# fpga.net
KiCad netlist of a schematic drawn in Altium Designer
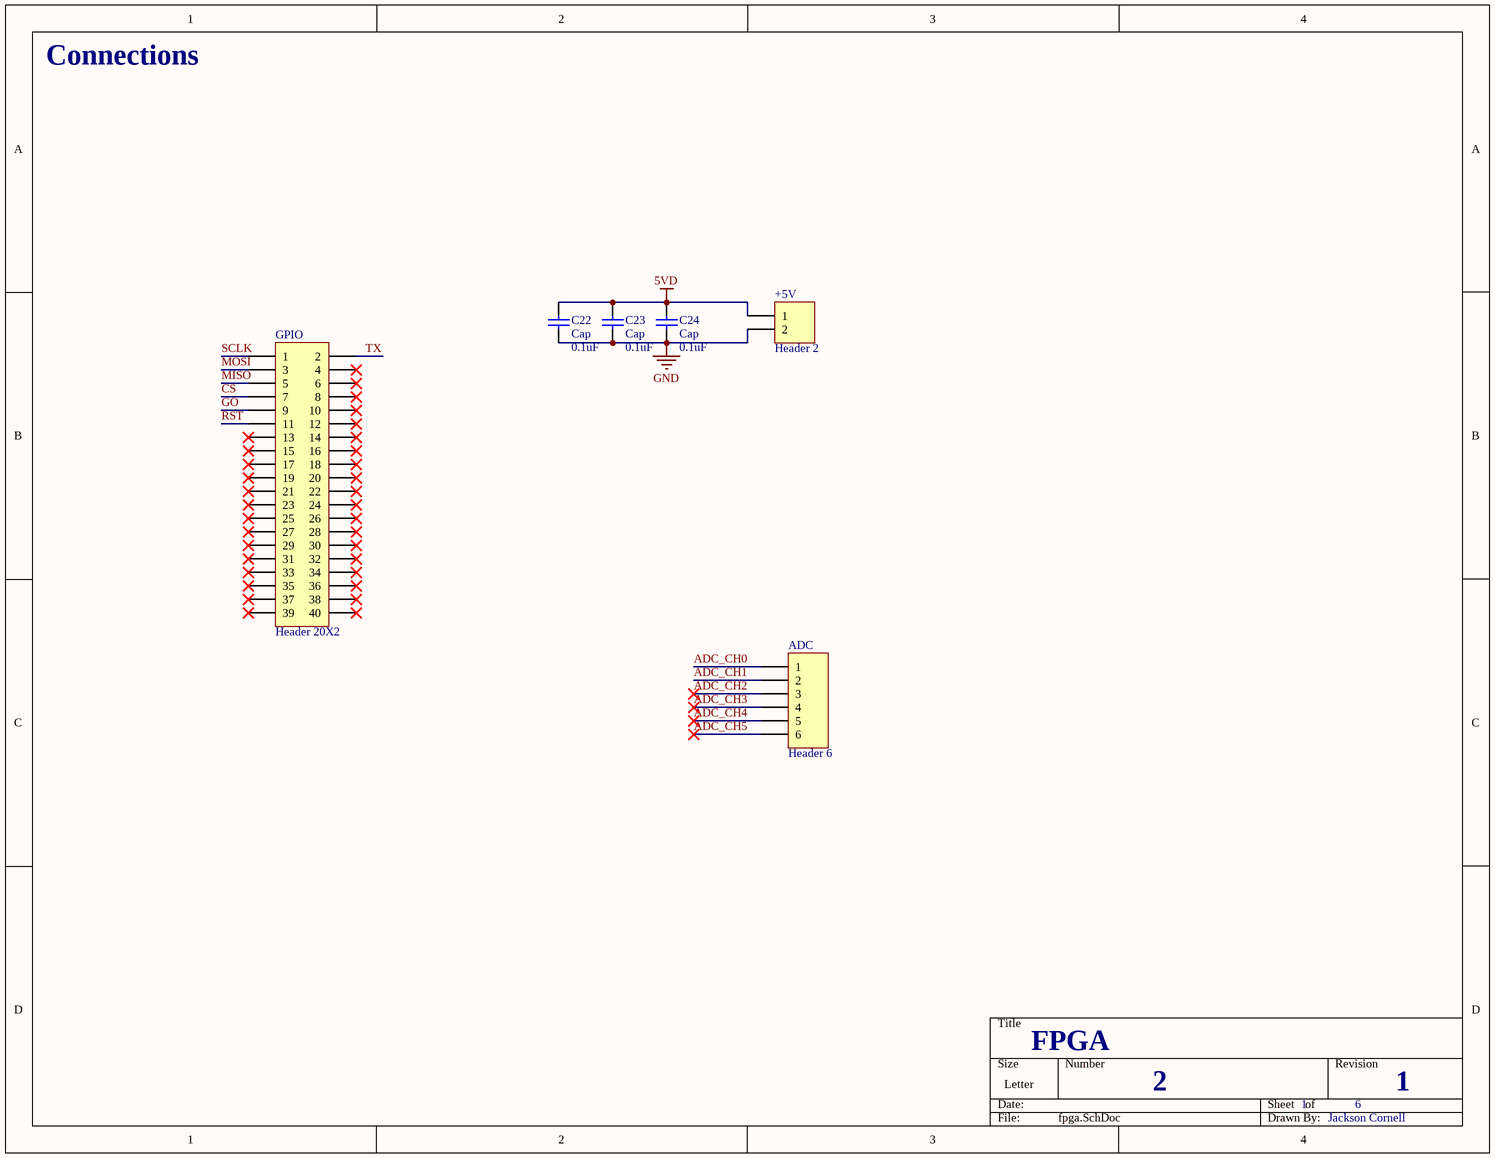
[diagram p0: fpga.SchDoc]

(export (version "E")
  (design (tool "Eeschema 10.0.6"))
  (components
    (comp (ref "+5V")
      (value "Header 2")
      (footprint "HDR1X2")
      (description "Header, 2-Pin")
      (fields (field (name "PUBLISHER") "Altium Limited"))
      (libsource (lib "Miscellaneous Connectors") (part "Header 2"))
    )
    (comp (ref "ADC")
      (value "Header 6")
      (footprint "HDR1X6")
      (description "Header, 6-Pin")
      (fields (field (name "PUBLISHER") "Altium Limited"))
      (libsource (lib "Miscellaneous Connectors") (part "Header 6"))
    )
    (comp (ref "C22")
      (value "Cap")
      (footprint "CAPC0805")
      (description "Capacitor")
      (fields (field (name "ALTIUM_VALUE") "0.1uF") (field (name "PUBLISHER") "Altium Limited"))
      (libsource (lib "Miscellaneous Devices") (part "Cap"))
    )
    (comp (ref "C23")
      (value "Cap")
      (footprint "CAPC0805")
      (description "Capacitor")
      (fields (field (name "ALTIUM_VALUE") "0.1uF") (field (name "PUBLISHER") "Altium Limited"))
      (libsource (lib "Miscellaneous Devices") (part "Cap"))
    )
    (comp (ref "C24")
      (value "Cap")
      (footprint "CAPC0805")
      (description "Capacitor")
      (fields (field (name "ALTIUM_VALUE") "0.1uF") (field (name "PUBLISHER") "Altium Limited"))
      (libsource (lib "Miscellaneous Devices") (part "Cap"))
    )
    (comp (ref "GPIO")
      (value "Header 20X2")
      (footprint "HDR2X20")
      (description "Header, 20-Pin, Dual row")
      (fields (field (name "PUBLISHER") "Altium Limited"))
      (libsource (lib "Miscellaneous Connectors") (part "Header 20X2"))
    )
  )
  (nets
    (net (code "1") (name "/ADC_CH0") (class "Default")
      (node (ref "ADC") (pin "1") (pinfunction "1_1") (pintype "passive"))
    )
    (net (code "2") (name "/ADC_CH1") (class "Default")
      (node (ref "ADC") (pin "2") (pinfunction "2_2") (pintype "passive"))
    )
    (net (code "3") (name "/ADC_CH2") (class "Default")
      (node (ref "ADC") (pin "3") (pinfunction "3_3") (pintype "passive+no_connect"))
    )
    (net (code "4") (name "/ADC_CH3") (class "Default")
      (node (ref "ADC") (pin "4") (pinfunction "4_4") (pintype "passive+no_connect"))
    )
    (net (code "5") (name "/ADC_CH4") (class "Default")
      (node (ref "ADC") (pin "5") (pinfunction "5_5") (pintype "passive+no_connect"))
    )
    (net (code "6") (name "/ADC_CH5") (class "Default")
      (node (ref "ADC") (pin "6") (pinfunction "6_6") (pintype "passive+no_connect"))
    )
    (net (code "7") (name "/CS") (class "Default")
      (node (ref "GPIO") (pin "7") (pinfunction "7_7") (pintype "passive"))
    )
    (net (code "8") (name "/GO") (class "Default")
      (node (ref "GPIO") (pin "9") (pinfunction "9_9") (pintype "passive"))
    )
    (net (code "9") (name "/MISO") (class "Default")
      (node (ref "GPIO") (pin "5") (pinfunction "5_5") (pintype "passive"))
    )
    (net (code "10") (name "/MOSI") (class "Default")
      (node (ref "GPIO") (pin "3") (pinfunction "3_3") (pintype "passive"))
    )
    (net (code "11") (name "/RST") (class "Default")
      (node (ref "GPIO") (pin "11") (pinfunction "11_11") (pintype "passive"))
    )
    (net (code "12") (name "/SCLK") (class "Default")
      (node (ref "GPIO") (pin "1") (pinfunction "1_1") (pintype "passive"))
    )
    (net (code "13") (name "/TX") (class "Default")
      (node (ref "GPIO") (pin "2") (pinfunction "2_2") (pintype "passive"))
    )
    (net (code "14") (name "5VD") (class "Default")
      (node (ref "+5V") (pin "1") (pinfunction "1_1") (pintype "passive"))
      (node (ref "C22") (pin "2") (pinfunction "2_2") (pintype "passive"))
      (node (ref "C23") (pin "2") (pinfunction "2_2") (pintype "passive"))
      (node (ref "C24") (pin "2") (pinfunction "2_2") (pintype "passive"))
    )
    (net (code "15") (name "GND") (class "Default")
      (node (ref "+5V") (pin "2") (pinfunction "2_2") (pintype "passive"))
      (node (ref "C22") (pin "1") (pinfunction "1_1") (pintype "passive"))
      (node (ref "C23") (pin "1") (pinfunction "1_1") (pintype "passive"))
      (node (ref "C24") (pin "1") (pinfunction "1_1") (pintype "passive"))
    )
    (net (code "16") (name "unconnected-(GPIO-Pad4)") (class "Default")
      (node (ref "GPIO") (pin "4") (pinfunction "4_4") (pintype "passive+no_connect"))
    )
    (net (code "17") (name "unconnected-(GPIO-Pad6)") (class "Default")
      (node (ref "GPIO") (pin "6") (pinfunction "6_6") (pintype "passive+no_connect"))
    )
    (net (code "18") (name "unconnected-(GPIO-Pad8)") (class "Default")
      (node (ref "GPIO") (pin "8") (pinfunction "8_8") (pintype "passive+no_connect"))
    )
    (net (code "19") (name "unconnected-(GPIO-Pad10)") (class "Default")
      (node (ref "GPIO") (pin "10") (pinfunction "10_10") (pintype "passive+no_connect"))
    )
    (net (code "20") (name "unconnected-(GPIO-Pad12)") (class "Default")
      (node (ref "GPIO") (pin "12") (pinfunction "12_12") (pintype "passive+no_connect"))
    )
    (net (code "21") (name "unconnected-(GPIO-Pad13)") (class "Default")
      (node (ref "GPIO") (pin "13") (pinfunction "13_13") (pintype "passive+no_connect"))
    )
    (net (code "22") (name "unconnected-(GPIO-Pad14)") (class "Default")
      (node (ref "GPIO") (pin "14") (pinfunction "14_14") (pintype "passive+no_connect"))
    )
    (net (code "23") (name "unconnected-(GPIO-Pad15)") (class "Default")
      (node (ref "GPIO") (pin "15") (pinfunction "15_15") (pintype "passive+no_connect"))
    )
    (net (code "24") (name "unconnected-(GPIO-Pad16)") (class "Default")
      (node (ref "GPIO") (pin "16") (pinfunction "16_16") (pintype "passive+no_connect"))
    )
    (net (code "25") (name "unconnected-(GPIO-Pad17)") (class "Default")
      (node (ref "GPIO") (pin "17") (pinfunction "17_17") (pintype "passive+no_connect"))
    )
    (net (code "26") (name "unconnected-(GPIO-Pad18)") (class "Default")
      (node (ref "GPIO") (pin "18") (pinfunction "18_18") (pintype "passive+no_connect"))
    )
    (net (code "27") (name "unconnected-(GPIO-Pad19)") (class "Default")
      (node (ref "GPIO") (pin "19") (pinfunction "19_19") (pintype "passive+no_connect"))
    )
    (net (code "28") (name "unconnected-(GPIO-Pad20)") (class "Default")
      (node (ref "GPIO") (pin "20") (pinfunction "20_20") (pintype "passive+no_connect"))
    )
    (net (code "29") (name "unconnected-(GPIO-Pad21)") (class "Default")
      (node (ref "GPIO") (pin "21") (pinfunction "21_21") (pintype "passive+no_connect"))
    )
    (net (code "30") (name "unconnected-(GPIO-Pad22)") (class "Default")
      (node (ref "GPIO") (pin "22") (pinfunction "22_22") (pintype "passive+no_connect"))
    )
    (net (code "31") (name "unconnected-(GPIO-Pad23)") (class "Default")
      (node (ref "GPIO") (pin "23") (pinfunction "23_23") (pintype "passive+no_connect"))
    )
    (net (code "32") (name "unconnected-(GPIO-Pad24)") (class "Default")
      (node (ref "GPIO") (pin "24") (pinfunction "24_24") (pintype "passive+no_connect"))
    )
    (net (code "33") (name "unconnected-(GPIO-Pad25)") (class "Default")
      (node (ref "GPIO") (pin "25") (pinfunction "25_25") (pintype "passive+no_connect"))
    )
    (net (code "34") (name "unconnected-(GPIO-Pad26)") (class "Default")
      (node (ref "GPIO") (pin "26") (pinfunction "26_26") (pintype "passive+no_connect"))
    )
    (net (code "35") (name "unconnected-(GPIO-Pad27)") (class "Default")
      (node (ref "GPIO") (pin "27") (pinfunction "27_27") (pintype "passive+no_connect"))
    )
    (net (code "36") (name "unconnected-(GPIO-Pad28)") (class "Default")
      (node (ref "GPIO") (pin "28") (pinfunction "28_28") (pintype "passive+no_connect"))
    )
    (net (code "37") (name "unconnected-(GPIO-Pad29)") (class "Default")
      (node (ref "GPIO") (pin "29") (pinfunction "29_29") (pintype "passive+no_connect"))
    )
    (net (code "38") (name "unconnected-(GPIO-Pad30)") (class "Default")
      (node (ref "GPIO") (pin "30") (pinfunction "30_30") (pintype "passive+no_connect"))
    )
    (net (code "39") (name "unconnected-(GPIO-Pad31)") (class "Default")
      (node (ref "GPIO") (pin "31") (pinfunction "31_31") (pintype "passive+no_connect"))
    )
    (net (code "40") (name "unconnected-(GPIO-Pad32)") (class "Default")
      (node (ref "GPIO") (pin "32") (pinfunction "32_32") (pintype "passive+no_connect"))
    )
    (net (code "41") (name "unconnected-(GPIO-Pad33)") (class "Default")
      (node (ref "GPIO") (pin "33") (pinfunction "33_33") (pintype "passive+no_connect"))
    )
    (net (code "42") (name "unconnected-(GPIO-Pad34)") (class "Default")
      (node (ref "GPIO") (pin "34") (pinfunction "34_34") (pintype "passive+no_connect"))
    )
    (net (code "43") (name "unconnected-(GPIO-Pad35)") (class "Default")
      (node (ref "GPIO") (pin "35") (pinfunction "35_35") (pintype "passive+no_connect"))
    )
    (net (code "44") (name "unconnected-(GPIO-Pad36)") (class "Default")
      (node (ref "GPIO") (pin "36") (pinfunction "36_36") (pintype "passive+no_connect"))
    )
    (net (code "45") (name "unconnected-(GPIO-Pad37)") (class "Default")
      (node (ref "GPIO") (pin "37") (pinfunction "37_37") (pintype "passive+no_connect"))
    )
    (net (code "46") (name "unconnected-(GPIO-Pad38)") (class "Default")
      (node (ref "GPIO") (pin "38") (pinfunction "38_38") (pintype "passive+no_connect"))
    )
    (net (code "47") (name "unconnected-(GPIO-Pad39)") (class "Default")
      (node (ref "GPIO") (pin "39") (pinfunction "39_39") (pintype "passive+no_connect"))
    )
    (net (code "48") (name "unconnected-(GPIO-Pad40)") (class "Default")
      (node (ref "GPIO") (pin "40") (pinfunction "40_40") (pintype "passive+no_connect"))
    )
  )
)
